# HDMI_CEC.net
KiCad netlist of a schematic drawn in Altium Designer
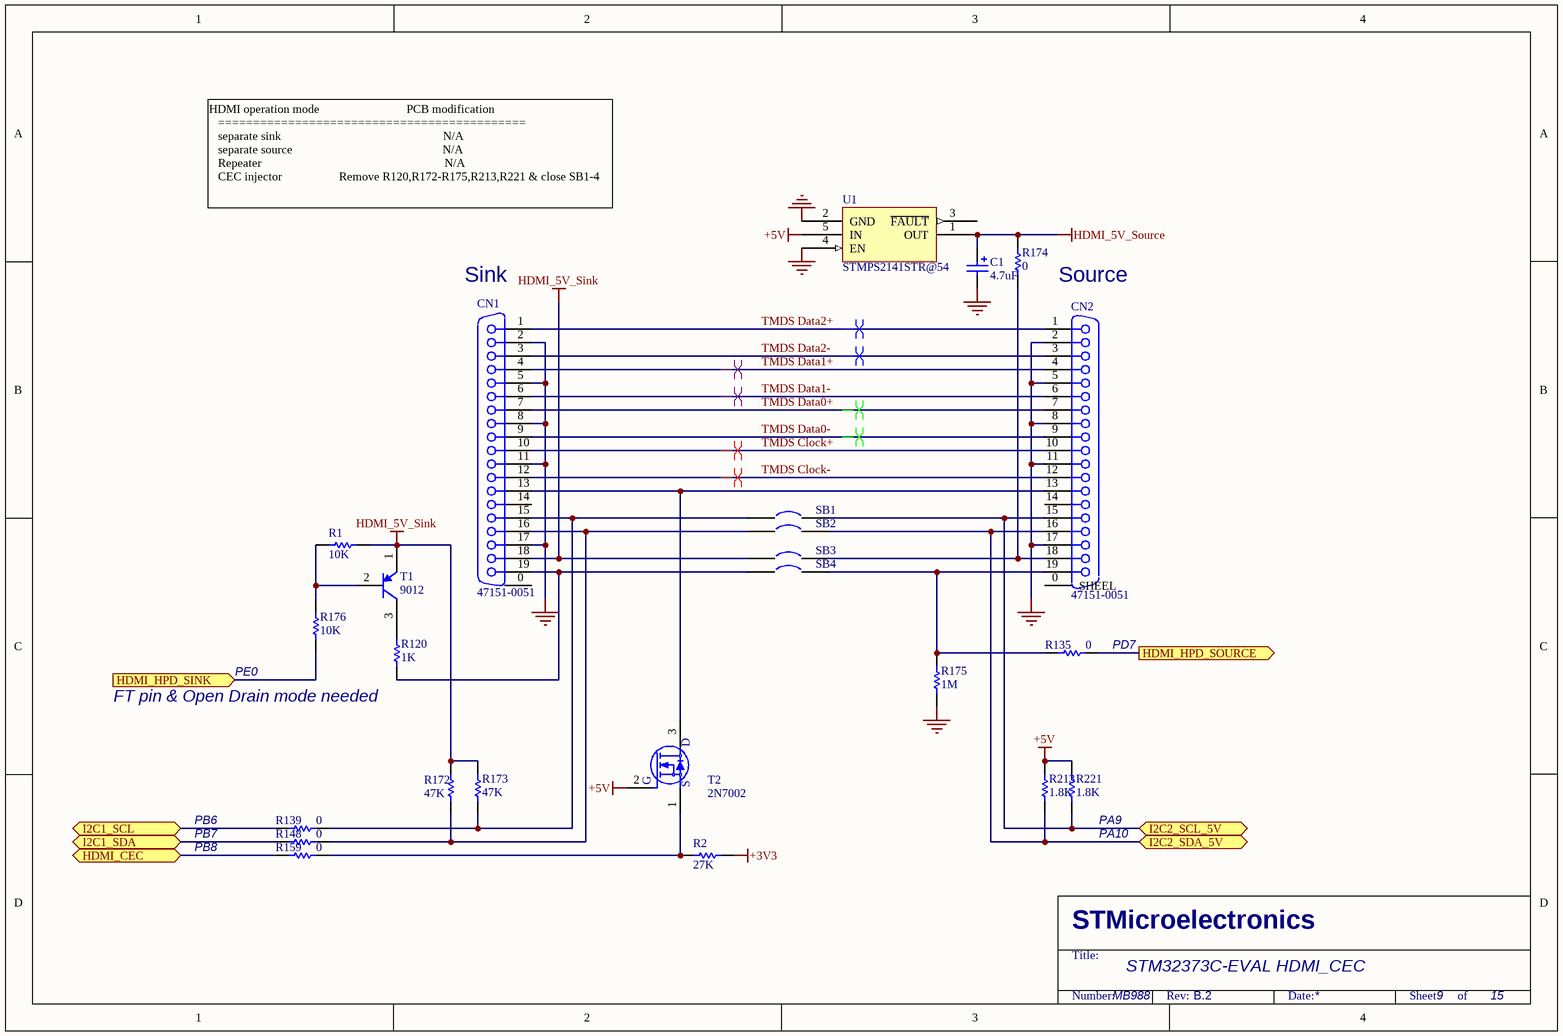
[diagram p0: HDMI_CEC.SchDoc]

(export (version "E")
  (design (tool "Eeschema 10.0.6"))
  (components
    (comp (ref "C1")
      (value "4.7uF")
      (footprint "TAN-A")
      (description "Polarized Capacitor (Radial)")
      (fields (field (name "PUBLISHER") "Altium Limited"))
      (libsource (lib "Miscellaneous Devices") (part "Cap Pol1"))
    )
    (comp (ref "CN1")
      (value "47151-0051")
      (footprint "0471510051")
      (libsource (lib "*") (part "47151-0051(L)"))
    )
    (comp (ref "CN2")
      (value "47151-0051")
      (footprint "0471510051")
      (libsource (lib "*") (part "47151-0051(R)"))
    )
    (comp (ref "R1")
      (value "10K")
      (footprint "0603R")
      (description "Resistor")
      (fields (field (name "PUBLISHER") "Altium Limited"))
      (libsource (lib "Miscellaneous Devices") (part "Res1"))
    )
    (comp (ref "R2")
      (value "27K")
      (footprint "0603R")
      (description "Resistor")
      (fields (field (name "PUBLISHER") "Altium Limited"))
      (libsource (lib "Miscellaneous Devices") (part "Res1"))
    )
    (comp (ref "R120")
      (value "1K")
      (footprint "0603R")
      (description "Resistor")
      (fields (field (name "PUBLISHER") "Altium Limited"))
      (libsource (lib "Miscellaneous Devices") (part "Res1"))
    )
    (comp (ref "R135")
      (value "0")
      (footprint "0603R")
      (description "Resistor")
      (fields (field (name "PUBLISHER") "Altium Limited"))
      (libsource (lib "Miscellaneous Devices") (part "Res1"))
    )
    (comp (ref "R139")
      (value "0")
      (footprint "0603R")
      (description "Resistor")
      (fields (field (name "PUBLISHER") "Altium Limited"))
      (libsource (lib "Miscellaneous Devices") (part "Res1"))
    )
    (comp (ref "R148")
      (value "0")
      (footprint "0603R")
      (description "Resistor")
      (fields (field (name "PUBLISHER") "Altium Limited"))
      (libsource (lib "Miscellaneous Devices") (part "Res1"))
    )
    (comp (ref "R159")
      (value "0")
      (footprint "0603R")
      (description "Resistor")
      (fields (field (name "PUBLISHER") "Altium Limited"))
      (libsource (lib "Miscellaneous Devices") (part "Res1"))
    )
    (comp (ref "R172")
      (value "47K")
      (footprint "0603R")
      (description "Resistor")
      (fields (field (name "PUBLISHER") "Altium Limited"))
      (libsource (lib "Miscellaneous Devices") (part "Res1"))
    )
    (comp (ref "R173")
      (value "47K")
      (footprint "0603R")
      (description "Resistor")
      (fields (field (name "PUBLISHER") "Altium Limited"))
      (libsource (lib "Miscellaneous Devices") (part "Res1"))
    )
    (comp (ref "R174")
      (value "0")
      (footprint "0603R")
      (description "Resistor")
      (fields (field (name "PUBLISHER") "Altium Limited"))
      (libsource (lib "Miscellaneous Devices") (part "Res1"))
    )
    (comp (ref "R175")
      (value "1M")
      (footprint "0603R")
      (description "Resistor")
      (fields (field (name "PUBLISHER") "Altium Limited"))
      (libsource (lib "Miscellaneous Devices") (part "Res1"))
    )
    (comp (ref "R176")
      (value "10K")
      (footprint "0603R")
      (description "Resistor")
      (fields (field (name "PUBLISHER") "Altium Limited"))
      (libsource (lib "Miscellaneous Devices") (part "Res1"))
    )
    (comp (ref "R213")
      (value "1.8K")
      (footprint "0603R")
      (description "Resistor")
      (fields (field (name "PUBLISHER") "Altium Limited"))
      (libsource (lib "Miscellaneous Devices") (part "Res1"))
    )
    (comp (ref "R221")
      (value "1.8K")
      (footprint "0603R")
      (description "Resistor")
      (fields (field (name "PUBLISHER") "Altium Limited"))
      (libsource (lib "Miscellaneous Devices") (part "Res1"))
    )
    (comp (ref "SB1")
      (value "~")
      (footprint "JP2_SMD")
      (description "Circuit Breaker")
      (fields (field (name "PUBLISHER") "Altium Limited"))
      (libsource (lib "Miscellaneous Devices") (part "Circuit Breaker"))
    )
    (comp (ref "SB2")
      (value "~")
      (footprint "JP2_SMD")
      (description "Circuit Breaker")
      (fields (field (name "PUBLISHER") "Altium Limited"))
      (libsource (lib "Miscellaneous Devices") (part "Circuit Breaker"))
    )
    (comp (ref "SB3")
      (value "~")
      (footprint "JP2_SMD")
      (description "Circuit Breaker")
      (fields (field (name "PUBLISHER") "Altium Limited"))
      (libsource (lib "Miscellaneous Devices") (part "Circuit Breaker"))
    )
    (comp (ref "SB4")
      (value "~")
      (footprint "JP2_SMD")
      (description "Circuit Breaker")
      (fields (field (name "PUBLISHER") "Altium Limited"))
      (libsource (lib "Miscellaneous Devices") (part "Circuit Breaker"))
    )
    (comp (ref "T1")
      (value "9012")
      (footprint "SOT-23")
      (description "PNP Bipolar Transistor")
      (fields (field (name "PUBLISHER") "Altium Limited"))
      (libsource (lib "Miscellaneous Devices") (part "PNP"))
    )
    (comp (ref "T2") (value "2N7002") (footprint "SOT-23") (libsource (lib "MB988") (part "2N7002")))
    (comp (ref "U1")
      (value "STMPS2141STR@54")
      (footprint "SOT-23-5L")
      (libsource (lib "MB784") (part "STMPS2141STR"))
    )
  )
  (nets
    (net (code "1") (name "+3V3") (class "Default")
      (node (ref "R2") (pin "2") (pinfunction "2_2") (pintype "passive"))
    )
    (net (code "2") (name "+5V") (class "Default")
      (node (ref "R213") (pin "2") (pinfunction "2_2") (pintype "passive"))
      (node (ref "R221") (pin "2") (pinfunction "2_2") (pintype "passive"))
      (node (ref "T2") (pin "2") (pinfunction "G_2") (pintype "passive"))
      (node (ref "U1") (pin "5") (pinfunction "IN_5") (pintype "passive"))
    )
    (net (code "3") (name "/HDMI_CEC") (class "Default")
      (node (ref "R159") (pin "2") (pinfunction "2_2") (pintype "passive"))
    )
    (net (code "4") (name "/HDMI_HPD_SINK") (class "Default")
      (node (ref "R176") (pin "1") (pinfunction "1_1") (pintype "passive"))
    )
    (net (code "5") (name "/HDMI_HPD_SOURCE") (class "Default")
      (node (ref "R135") (pin "1") (pinfunction "1_1") (pintype "passive"))
    )
    (net (code "6") (name "/I2C1_SCL") (class "Default")
      (node (ref "R139") (pin "2") (pinfunction "2_2") (pintype "passive"))
    )
    (net (code "7") (name "/I2C1_SDA") (class "Default")
      (node (ref "R148") (pin "2") (pinfunction "2_2") (pintype "passive"))
    )
    (net (code "8") (name "/I2C2_SCL_5V") (class "Default")
      (node (ref "CN2") (pin "15") (pinfunction "15_15") (pintype "passive"))
      (node (ref "R221") (pin "1") (pinfunction "1_1") (pintype "passive"))
      (node (ref "SB1") (pin "2") (pinfunction "2_2") (pintype "passive"))
    )
    (net (code "9") (name "/I2C2_SDA_5V") (class "Default")
      (node (ref "CN2") (pin "16") (pinfunction "16_16") (pintype "passive"))
      (node (ref "R213") (pin "1") (pinfunction "1_1") (pintype "passive"))
      (node (ref "SB2") (pin "2") (pinfunction "2_2") (pintype "passive"))
    )
    (net (code "10") (name "/TMDS Clock+") (class "Default")
      (node (ref "CN1") (pin "10") (pinfunction "10_10") (pintype "passive"))
      (node (ref "CN2") (pin "10") (pinfunction "10_10") (pintype "passive"))
    )
    (net (code "11") (name "/TMDS Clock-") (class "Default")
      (node (ref "CN1") (pin "12") (pinfunction "12_12") (pintype "passive"))
      (node (ref "CN2") (pin "12") (pinfunction "12_12") (pintype "passive"))
    )
    (net (code "12") (name "/TMDS Data0+") (class "Default")
      (node (ref "CN1") (pin "7") (pinfunction "7_7") (pintype "passive"))
      (node (ref "CN2") (pin "7") (pinfunction "7_7") (pintype "passive"))
    )
    (net (code "13") (name "/TMDS Data0-") (class "Default")
      (node (ref "CN1") (pin "9") (pinfunction "9_9") (pintype "passive"))
      (node (ref "CN2") (pin "9") (pinfunction "9_9") (pintype "passive"))
    )
    (net (code "14") (name "/TMDS Data1+") (class "Default")
      (node (ref "CN1") (pin "4") (pinfunction "4_4") (pintype "passive"))
      (node (ref "CN2") (pin "4") (pinfunction "4_4") (pintype "passive"))
    )
    (net (code "15") (name "/TMDS Data1-") (class "Default")
      (node (ref "CN1") (pin "6") (pinfunction "6_6") (pintype "passive"))
      (node (ref "CN2") (pin "6") (pinfunction "6_6") (pintype "passive"))
    )
    (net (code "16") (name "/TMDS Data2+") (class "Default")
      (node (ref "CN1") (pin "1") (pinfunction "1_1") (pintype "passive"))
      (node (ref "CN2") (pin "1") (pinfunction "1_1") (pintype "passive"))
    )
    (net (code "17") (name "/TMDS Data2-") (class "Default")
      (node (ref "CN1") (pin "3") (pinfunction "3_3") (pintype "passive"))
      (node (ref "CN2") (pin "3") (pinfunction "3_3") (pintype "passive"))
    )
    (net (code "18") (name "GND") (class "Default")
      (node (ref "C1") (pin "2") (pinfunction "2_2") (pintype "passive"))
      (node (ref "CN1") (pin "11") (pinfunction "11_11") (pintype "passive"))
      (node (ref "CN1") (pin "17") (pinfunction "17_17") (pintype "passive"))
      (node (ref "CN1") (pin "2") (pinfunction "2_2") (pintype "passive"))
      (node (ref "CN1") (pin "5") (pinfunction "5_5") (pintype "passive"))
      (node (ref "CN1") (pin "8") (pinfunction "8_8") (pintype "passive"))
      (node (ref "CN2") (pin "11") (pinfunction "11_11") (pintype "passive"))
      (node (ref "CN2") (pin "17") (pinfunction "17_17") (pintype "passive"))
      (node (ref "CN2") (pin "2") (pinfunction "2_2") (pintype "passive"))
      (node (ref "CN2") (pin "5") (pinfunction "5_5") (pintype "passive"))
      (node (ref "CN2") (pin "8") (pinfunction "8_8") (pintype "passive"))
      (node (ref "R175") (pin "1") (pinfunction "1_1") (pintype "passive"))
      (node (ref "U1") (pin "2") (pinfunction "GND_2") (pintype "passive"))
      (node (ref "U1") (pin "4") (pinfunction "EN_4") (pintype "input"))
    )
    (net (code "19") (name "HDMI_5V_Sink") (class "Default")
      (node (ref "CN1") (pin "18") (pinfunction "18_18") (pintype "passive"))
      (node (ref "R1") (pin "1") (pinfunction "1_1") (pintype "passive"))
      (node (ref "R172") (pin "2") (pinfunction "2_2") (pintype "passive"))
      (node (ref "R173") (pin "2") (pinfunction "2_2") (pintype "passive"))
      (node (ref "SB3") (pin "1") (pinfunction "1_1") (pintype "passive"))
      (node (ref "T1") (pin "1") (pinfunction "E_1") (pintype "passive"))
    )
    (net (code "20") (name "HDMI_5V_Source") (class "Default")
      (node (ref "C1") (pin "1") (pinfunction "1_1") (pintype "passive"))
      (node (ref "R174") (pin "1") (pinfunction "1_1") (pintype "passive"))
      (node (ref "U1") (pin "1") (pinfunction "OUT_1") (pintype "passive"))
    )
    (net (code "21") (name "Net-(CN1-Pad15)") (class "Default")
      (node (ref "CN1") (pin "15") (pinfunction "15_15") (pintype "passive"))
      (node (ref "R139") (pin "1") (pinfunction "1_1") (pintype "passive"))
      (node (ref "R173") (pin "1") (pinfunction "1_1") (pintype "passive"))
      (node (ref "SB1") (pin "1") (pinfunction "1_1") (pintype "passive"))
    )
    (net (code "22") (name "Net-(CN1-Pad16)") (class "Default")
      (node (ref "CN1") (pin "16") (pinfunction "16_16") (pintype "passive"))
      (node (ref "R148") (pin "1") (pinfunction "1_1") (pintype "passive"))
      (node (ref "R172") (pin "1") (pinfunction "1_1") (pintype "passive"))
      (node (ref "SB2") (pin "1") (pinfunction "1_1") (pintype "passive"))
    )
    (net (code "23") (name "Net-(CN1-Pad19)") (class "Default")
      (node (ref "CN1") (pin "19") (pinfunction "19_19") (pintype "passive"))
      (node (ref "R120") (pin "1") (pinfunction "1_1") (pintype "passive"))
      (node (ref "SB4") (pin "1") (pinfunction "1_1") (pintype "passive"))
    )
    (net (code "24") (name "Net-(CN2-Pad18)") (class "Default")
      (node (ref "CN2") (pin "18") (pinfunction "18_18") (pintype "passive"))
      (node (ref "R174") (pin "2") (pinfunction "2_2") (pintype "passive"))
      (node (ref "SB3") (pin "2") (pinfunction "2_2") (pintype "passive"))
    )
    (net (code "25") (name "Net-(CN2-Pad19)") (class "Default")
      (node (ref "CN2") (pin "19") (pinfunction "19_19") (pintype "passive"))
      (node (ref "R135") (pin "2") (pinfunction "2_2") (pintype "passive"))
      (node (ref "R175") (pin "2") (pinfunction "2_2") (pintype "passive"))
      (node (ref "SB4") (pin "2") (pinfunction "2_2") (pintype "passive"))
    )
    (net (code "26") (name "Net-(T1-B)") (class "Default")
      (node (ref "R1") (pin "2") (pinfunction "2_2") (pintype "passive"))
      (node (ref "R176") (pin "2") (pinfunction "2_2") (pintype "passive"))
      (node (ref "T1") (pin "2") (pinfunction "B_2") (pintype "passive"))
    )
    (net (code "27") (name "Net-(T1-C)") (class "Default")
      (node (ref "R120") (pin "2") (pinfunction "2_2") (pintype "passive"))
      (node (ref "T1") (pin "3") (pinfunction "C_3") (pintype "passive"))
    )
    (net (code "28") (name "Net-(T2-D)") (class "Default")
      (node (ref "CN1") (pin "13") (pinfunction "13_13") (pintype "passive"))
      (node (ref "CN2") (pin "13") (pinfunction "13_13") (pintype "passive"))
      (node (ref "T2") (pin "3") (pinfunction "D_3") (pintype "passive"))
    )
    (net (code "29") (name "Net-(T2-S)") (class "Default")
      (node (ref "R159") (pin "1") (pinfunction "1_1") (pintype "passive"))
      (node (ref "R2") (pin "1") (pinfunction "1_1") (pintype "passive"))
      (node (ref "T2") (pin "1") (pinfunction "S_1") (pintype "passive"))
    )
    (net (code "30") (name "unconnected-(CN1-Pad14)") (class "Default")
      (node (ref "CN1") (pin "14") (pinfunction "14_14") (pintype "passive"))
    )
    (net (code "31") (name "unconnected-(CN1-SHEEL-Pad0)") (class "Default")
      (node (ref "CN1") (pin "0") (pinfunction "SHEEL_0") (pintype "passive"))
    )
    (net (code "32") (name "unconnected-(CN2-Pad14)") (class "Default")
      (node (ref "CN2") (pin "14") (pinfunction "14_14") (pintype "passive"))
    )
    (net (code "33") (name "unconnected-(CN2-SHEEL-Pad0)") (class "Default")
      (node (ref "CN2") (pin "0") (pinfunction "SHEEL_0") (pintype "passive"))
    )
    (net (code "34") (name "unconnected-(U1-~{FAULT}-Pad3)") (class "Default")
      (node (ref "U1") (pin "3") (pinfunction "~{FAULT}_3") (pintype "output"))
    )
  )
)
